# MCISO-S02-V00-PSU5VB.net
KiCad netlist of a schematic drawn in Altium Designer
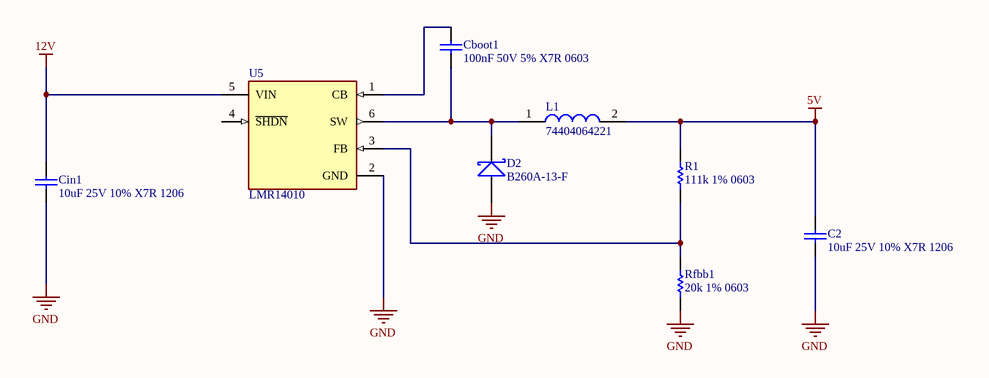
[diagram p0: MCISO-S02-V00-PSU5VB.SchDoc]

(export (version "E")
  (design (tool "Eeschema 10.0.6"))
  (components
    (comp (ref "C2")
      (value "10uF 25V 10% X7R 1206")
      (footprint "Cap_Ceramic_1206")
      (description "Capacitor, Ceramic, SMD, 10uF, 25V, 10%, X7R, 1206")
      (libsource (lib "QUTMS-MCISOLibrary") (part "10uF 25V 10% X7R 1206"))
    )
    (comp (ref "Cboot1")
      (value "100nF 50V 5% X7R 0603")
      (footprint "Cap_Ceramic_0603")
      (description "Capacitor, Ceramic, SMD, 100nF, 50V, 5%, X7R, 0603")
      (libsource (lib "StandardCapacitors") (part "100nF 50V 5% X7R 0603"))
    )
    (comp (ref "Cin1")
      (value "10uF 25V 10% X7R 1206")
      (footprint "Cap_Ceramic_1206")
      (description "Capacitor, Ceramic, SMD, 10uF, 25V, 10%, X7R, 1206")
      (libsource (lib "StandardCapacitors") (part "10uF 25V 10% X7R 1206"))
    )
    (comp (ref "D2")
      (value "B260A-13-F")
      (footprint "SMA")
      (description "Diode, Schottky Barrier Rectifier, 60 V, 2 A, B260A-13-F")
      (libsource (lib "QUTMS-MCISOLibrary") (part "B260A-13-F"))
    )
    (comp (ref "L1")
      (value "74404064221")
      (footprint "Inductor_6x6mm")
      (description "FIXED IND 220UH 660MA 850 MOHM")
      (libsource (lib "QUTMS_InductorLibrary") (part "74404064221"))
    )
    (comp (ref "R1")
      (value "111k 1% 0603")
      (footprint "Res_ThinFilm_0603")
      (description "Resistor, SMD, 111k, 0.1W, 1%, 0603")
      (libsource (lib "QUTMS-MCISOLibrary") (part "111k 1% 0603"))
    )
    (comp (ref "Rfbb1")
      (value "20k 1% 0603")
      (footprint "Res_ThinFilm_0603")
      (description "Resistor, SMD, 19k6, 0.1W, 5%, 0603")
      (libsource (lib "StandardResistors") (part "19k6 1% 0603"))
    )
    (comp (ref "U5")
      (value "LMR14010")
      (footprint "LMR14010")
      (libsource (lib "QUTMS_PowerSupplyLibrary") (part "LMR14010"))
    )
  )
  (nets
    (net (code "1") (name "5V") (class "Default")
      (node (ref "C2") (pin "2") (pinfunction "2_2") (pintype "passive"))
      (node (ref "L1") (pin "2") (pinfunction "2_2") (pintype "passive"))
      (node (ref "R1") (pin "2") (pinfunction "2_2") (pintype "passive"))
    )
    (net (code "2") (name "12V") (class "Default")
      (node (ref "Cin1") (pin "2") (pinfunction "2_2") (pintype "passive"))
      (node (ref "U5") (pin "5") (pinfunction "VIN_5") (pintype "power_in"))
    )
    (net (code "3") (name "GND") (class "Default")
      (node (ref "C2") (pin "1") (pinfunction "1_1") (pintype "passive"))
      (node (ref "Cin1") (pin "1") (pinfunction "1_1") (pintype "passive"))
      (node (ref "D2") (pin "A") (pinfunction "A_A") (pintype "passive"))
      (node (ref "Rfbb1") (pin "1") (pinfunction "1_1") (pintype "passive"))
      (node (ref "U5") (pin "2") (pinfunction "GND_2") (pintype "power_in"))
    )
    (net (code "4") (name "Net-(U5-CB)") (class "Default")
      (node (ref "Cboot1") (pin "2") (pinfunction "2_2") (pintype "passive"))
      (node (ref "U5") (pin "1") (pinfunction "CB_1") (pintype "input"))
    )
    (net (code "5") (name "Net-(U5-FB)") (class "Default")
      (node (ref "R1") (pin "1") (pinfunction "1_1") (pintype "passive"))
      (node (ref "Rfbb1") (pin "2") (pinfunction "2_2") (pintype "passive"))
      (node (ref "U5") (pin "3") (pinfunction "FB_3") (pintype "input"))
    )
    (net (code "6") (name "Net-(U5-SW)") (class "Default")
      (node (ref "Cboot1") (pin "1") (pinfunction "1_1") (pintype "passive"))
      (node (ref "D2") (pin "K") (pinfunction "K_K") (pintype "passive"))
      (node (ref "L1") (pin "1") (pinfunction "1_1") (pintype "passive"))
      (node (ref "U5") (pin "6") (pinfunction "SW_6") (pintype "output"))
    )
    (net (code "7") (name "unconnected-(U5-~{SHDN}-Pad4)") (class "Default")
      (node (ref "U5") (pin "4") (pinfunction "~{SHDN}_4") (pintype "input"))
    )
  )
)
